# ife18_TS_BMS_Master.net
KiCad netlist of a schematic drawn in Altium Designer
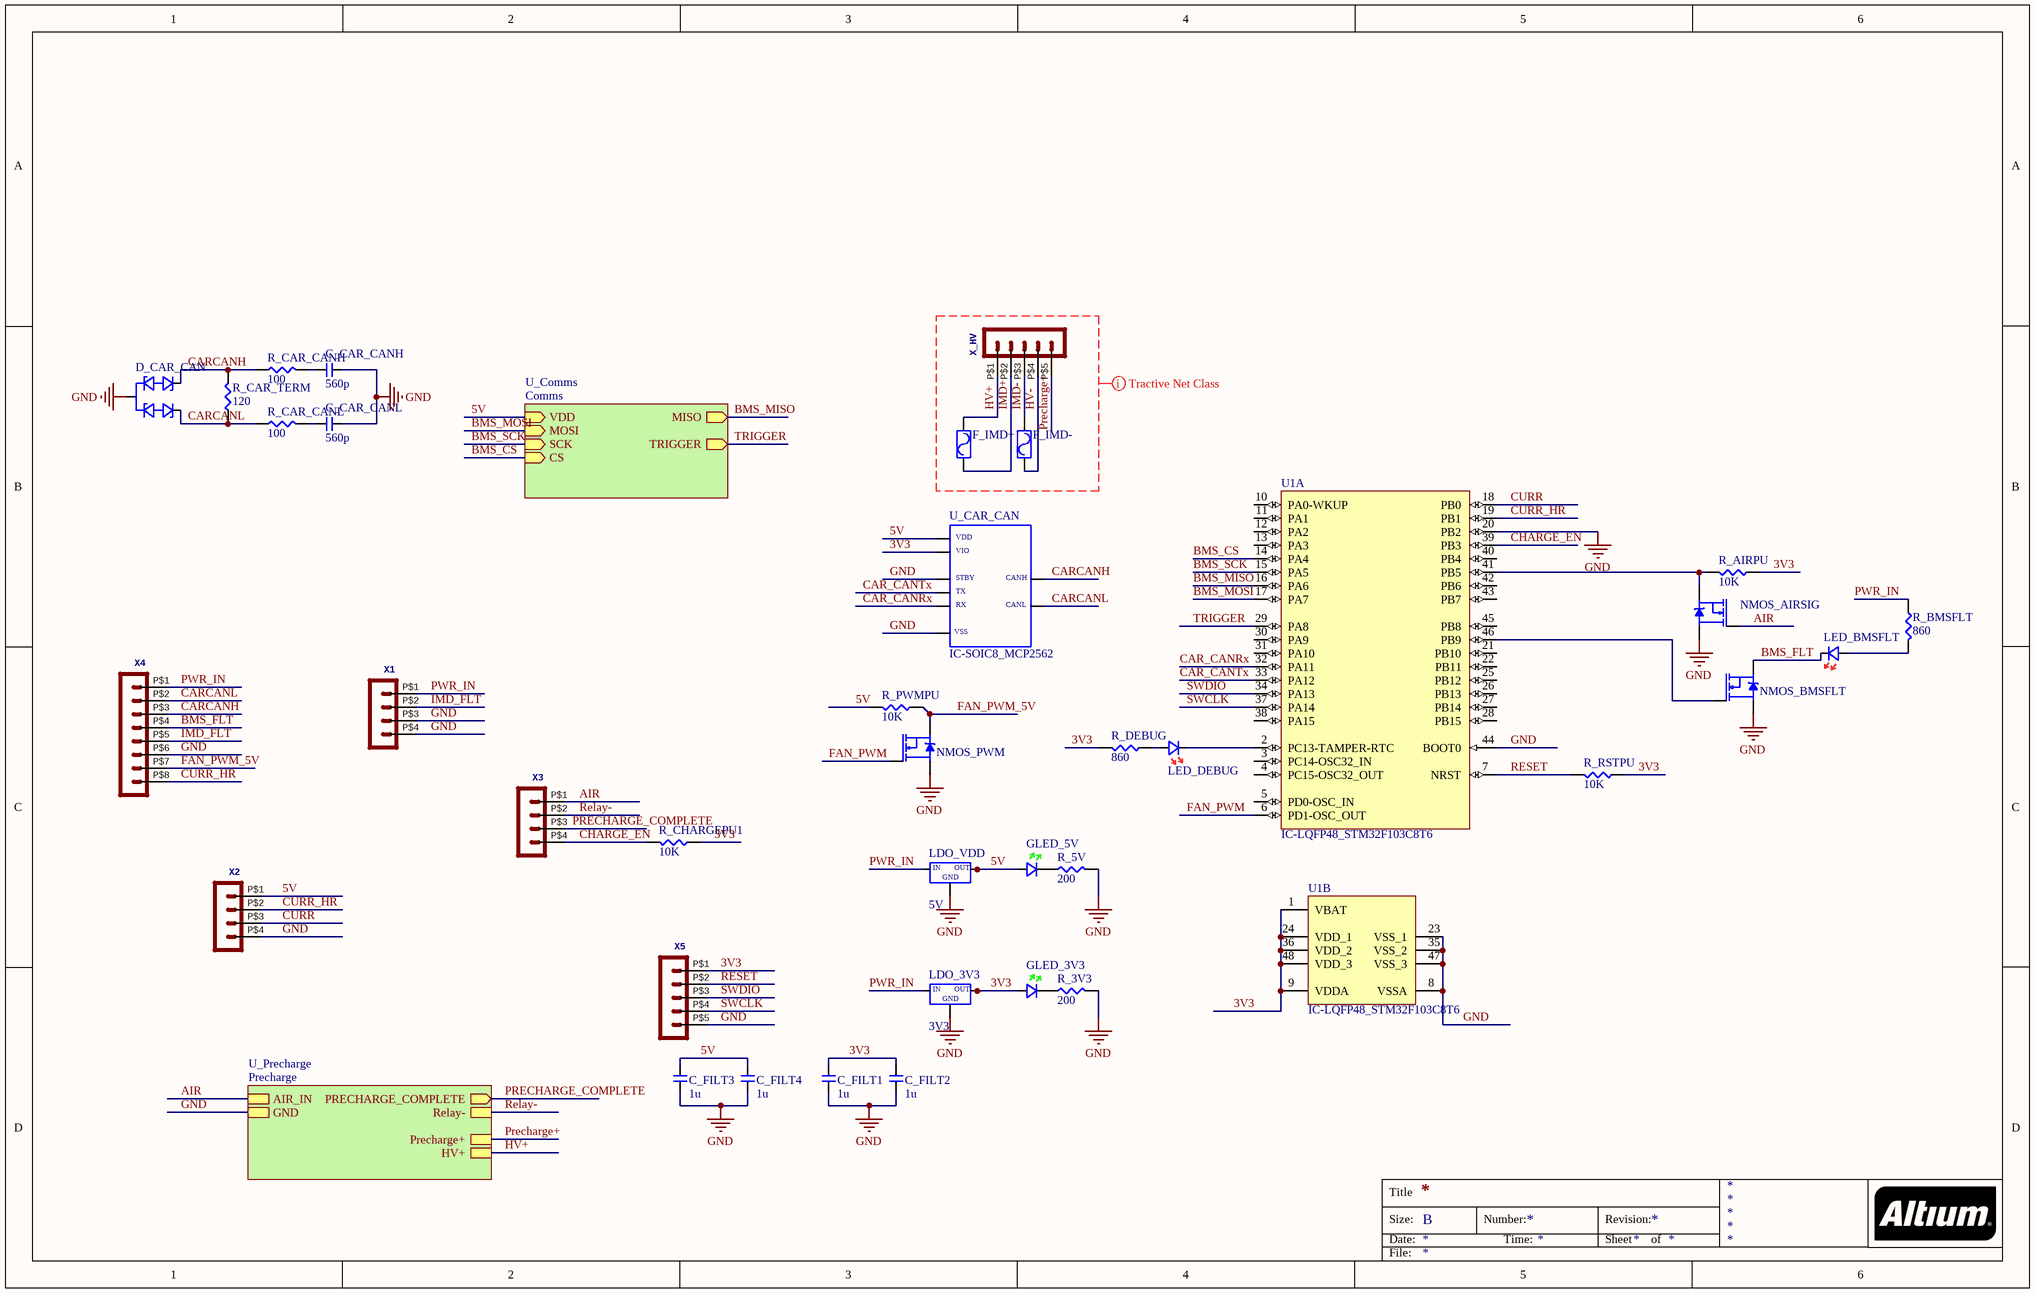
[diagram p0: ife18_TS_BMS_Master.SchDoc]

(export (version "E")
  (design (tool "Eeschema 10.0.6"))
  (components
    (comp (ref "C_CAR_CANH")
      (value "560p")
      (footprint "CAP-0603")
      (libsource (lib "altium-import") (part "root_0_CAP-0603_"))
    )
    (comp (ref "C_CAR_CANL")
      (value "560p")
      (footprint "CAP-0603")
      (libsource (lib "altium-import") (part "root_0_CAP-0603_"))
    )
    (comp (ref "C_FILT1")
      (value "1u")
      (footprint "CAP-0603")
      (libsource (lib "altium-import") (part "root_1_CAP-0603_"))
    )
    (comp (ref "C_FILT2")
      (value "1u")
      (footprint "CAP-0603")
      (libsource (lib "altium-import") (part "root_1_CAP-0603_"))
    )
    (comp (ref "C_FILT3")
      (value "1u")
      (footprint "CAP-0603")
      (libsource (lib "altium-import") (part "root_1_CAP-0603_"))
    )
    (comp (ref "C_FILT4")
      (value "1u")
      (footprint "CAP-0603")
      (libsource (lib "altium-import") (part "root_1_CAP-0603_"))
    )
    (comp (ref "D_CAR_CAN")
      (value "DIODE-SOT23_PESD1CAN")
      (footprint "SOT23")
      (libsource (lib "altium-import") (part "root_0_DIODE-SOT23_PESD1CAN_"))
    )
    (comp (ref "F_IMD+")
      (value "FUSE_885")
      (footprint "FUSE_885")
      (libsource (lib "ife19_Elec_Library") (part "FUSE_885"))
    )
    (comp (ref "F_IMD-")
      (value "FUSE_885")
      (footprint "FUSE_885")
      (libsource (lib "ife19_Elec_Library") (part "FUSE_885"))
    )
    (comp (ref "GLED_3V3")
      (value "~")
      (footprint "LEDGREEN-0603")
      (libsource (lib "altium-import") (part "root_0_LEDGREEN-0603_"))
    )
    (comp (ref "GLED_5V")
      (value "~")
      (footprint "LEDGREEN-0603")
      (libsource (lib "altium-import") (part "root_0_LEDGREEN-0603_"))
    )
    (comp (ref "LDO_3V3")
      (value "3V3")
      (footprint "SOT223")
      (libsource (lib "altium-import") (part "root_0_LDO-SOT223_SPX1117_"))
    )
    (comp (ref "LDO_VDD")
      (value "5V")
      (footprint "SOT223")
      (libsource (lib "altium-import") (part "root_0_LDO-SOT223_SPX1117_"))
    )
    (comp (ref "LED_BMSFLT")
      (value "LEDRED-0603")
      (footprint "LEDRED-0603")
      (libsource (lib "altium-import") (part "root_2_LEDRED-0603_"))
    )
    (comp (ref "LED_DEBUG")
      (value "LEDRED-0603")
      (footprint "LEDRED-0603")
      (libsource (lib "altium-import") (part "root_2_mirrored_LEDRED-0603_"))
    )
    (comp (ref "NMOS_AIRSIG")
      (value "NMOS-SOT23")
      (footprint "SOT23")
      (libsource (lib "altium-import") (part "root_0_NMOS-SOT23_"))
    )
    (comp (ref "NMOS_BMSFLT")
      (value "NMOS-SOT23")
      (footprint "SOT23")
      (libsource (lib "altium-import") (part "root_0_mirrored_NMOS-SOT23_"))
    )
    (comp (ref "NMOS_PWM")
      (value "NMOS-SOT23")
      (footprint "SOT23")
      (libsource (lib "altium-import") (part "root_0_mirrored_NMOS-SOT23_"))
    )
    (comp (ref "R_3V3")
      (value "200")
      (footprint "RES-0603")
      (libsource (lib "altium-import") (part "root_0_RES-0603_"))
    )
    (comp (ref "R_5V")
      (value "200")
      (footprint "RES-0603")
      (libsource (lib "altium-import") (part "root_0_RES-0603_"))
    )
    (comp (ref "R_AIRPU")
      (value "10K")
      (footprint "RES-0603")
      (libsource (lib "altium-import") (part "root_2_RES-0603_"))
    )
    (comp (ref "R_BMSFLT")
      (value "860")
      (footprint "RES-0603")
      (libsource (lib "altium-import") (part "root_1_mirrored_RES-0603_"))
    )
    (comp (ref "R_CAR_CANH")
      (value "100")
      (footprint "RES-0603")
      (libsource (lib "altium-import") (part "root_0_RES-0603_"))
    )
    (comp (ref "R_CAR_CANL")
      (value "100")
      (footprint "RES-0603")
      (libsource (lib "altium-import") (part "root_0_RES-0603_"))
    )
    (comp (ref "R_CAR_TERM")
      (value "120")
      (footprint "RES-0603")
      (libsource (lib "altium-import") (part "root_1_RES-0603_"))
    )
    (comp (ref "R_CHARGEPU1")
      (value "10K")
      (footprint "RES-0603")
      (libsource (lib "altium-import") (part "root_2_RES-0603_"))
    )
    (comp (ref "R_DEBUG")
      (value "860")
      (footprint "RES-0603")
      (libsource (lib "altium-import") (part "root_2_RES-0603_"))
    )
    (comp (ref "R_PWMPU")
      (value "10K")
      (footprint "RES-0603")
      (libsource (lib "altium-import") (part "root_2_mirrored_RES-0603_"))
    )
    (comp (ref "R_RSTPU")
      (value "10K")
      (footprint "RES-0603")
      (libsource (lib "altium-import") (part "root_2_RES-0603_"))
    )
    (comp (ref "U1")
      (value "IC-LQFP48_STM32F103C8T6")
      (footprint "STM-LQFP48_M")
      (fields (field (name "PARTNUMBER") "STM32F103C8T6"))
      (libsource (lib "ife19_Elec_Library") (part "IC-LQFP48_STM32F103C8T6"))
    )
    (comp (ref "U_CAR_CAN")
      (value "IC-SOIC8_MCP2562")
      (footprint "SOIC8")
      (libsource (lib "altium-import") (part "root_0_IC-SOIC8_MCP2562_"))
    )
    (comp (ref "X1")
      (value "Molex - Micro-Fit 3.0 Series connector,  3.00mm (0.118\") pitch header, 4 positions.")
      (footprint "43650-0424")
      (libsource (lib "ife19_Elec_Conn_Library") (part "POS4_MF43650-0424"))
    )
    (comp (ref "X2")
      (value "Molex - Micro-Fit 3.0 Series connector,  3.00mm (0.118\") pitch header, 4 positions.")
      (footprint "43650-0424")
      (libsource (lib "ife19_Elec_Conn_Library") (part "POS4_MF43650-0424"))
    )
    (comp (ref "X3")
      (value "Molex - Micro-Fit 3.0 Series connector,  3.00mm (0.118\") pitch header, 4 positions.")
      (footprint "43650-0424")
      (libsource (lib "ife19_Elec_Conn_Library") (part "POS4_MF43650-0424"))
    )
    (comp (ref "X4")
      (value "Molex - Micro-Fit 3.0 Series connector,  3.00mm (0.118\") pitch header, 8 positions.")
      (footprint "43650-0824")
      (libsource (lib "MOLEX Micro-Fit") (part "HEADER_POS8_?43650-0824"))
    )
    (comp (ref "X5")
      (value "~")
      (footprint "POS5_254MM_MALE")
      (libsource (lib "altium-import") (part "root_0_mirrored_POS5_254MM_MALE_"))
    )
    (comp (ref "X_HV")
      (value "Molex - Micro-Fit 3.0 Series connector,  3.00mm (0.118\") pitch header, 5 positions.")
      (footprint "43650-0524")
      (libsource (lib "ife19_Elec_Conn_Library") (part "POS5_MF43650-0524"))
    )
  )
  (nets
    (net (code "1") (name "/3V3") (class "Default")
      (node (ref "C_FILT1") (pin "2") (pinfunction "2_2") (pintype "passive"))
      (node (ref "C_FILT2") (pin "2") (pinfunction "2_2") (pintype "passive"))
      (node (ref "GLED_3V3") (pin "A") (pinfunction "A_A") (pintype "passive"))
      (node (ref "LDO_3V3") (pin "2") (pinfunction "2_2") (pintype "passive"))
      (node (ref "LDO_3V3") (pin "4") (pinfunction "4_4") (pintype "passive"))
      (node (ref "R_AIRPU") (pin "1") (pinfunction "1_1") (pintype "passive"))
      (node (ref "R_CHARGEPU1") (pin "1") (pinfunction "1_1") (pintype "passive"))
      (node (ref "R_DEBUG") (pin "2") (pinfunction "2_2") (pintype "passive"))
      (node (ref "R_RSTPU") (pin "1") (pinfunction "1_1") (pintype "passive"))
      (node (ref "U1") (pin "1") (pinfunction "VBAT_1") (pintype "power_in"))
      (node (ref "U1") (pin "24") (pinfunction "VDD_1_24") (pintype "power_in"))
      (node (ref "U1") (pin "36") (pinfunction "VDD_2_36") (pintype "power_in"))
      (node (ref "U1") (pin "48") (pinfunction "VDD_3_48") (pintype "power_in"))
      (node (ref "U1") (pin "9") (pinfunction "VDDA_9") (pintype "power_in"))
      (node (ref "U_CAR_CAN") (pin "5") (pinfunction "5_5") (pintype "passive"))
      (node (ref "X5") (pin "P$1") (pinfunction "1_P$1") (pintype "passive"))
    )
    (net (code "2") (name "/5V") (class "Default")
      (node (ref "C_FILT3") (pin "2") (pinfunction "2_2") (pintype "passive"))
      (node (ref "C_FILT4") (pin "2") (pinfunction "2_2") (pintype "passive"))
      (node (ref "GLED_5V") (pin "A") (pinfunction "A_A") (pintype "passive"))
      (node (ref "LDO_VDD") (pin "2") (pinfunction "2_2") (pintype "passive"))
      (node (ref "LDO_VDD") (pin "4") (pinfunction "4_4") (pintype "passive"))
      (node (ref "R_PWMPU") (pin "1") (pinfunction "1_1") (pintype "passive"))
      (node (ref "U_CAR_CAN") (pin "3") (pinfunction "3_3") (pintype "passive"))
      (node (ref "X2") (pin "P$1") (pinfunction "1_P$1") (pintype "passive"))
    )
    (net (code "3") (name "/AIR") (class "Default")
      (node (ref "NMOS_AIRSIG") (pin "1") (pinfunction "G_1") (pintype "passive"))
      (node (ref "X3") (pin "P$1") (pinfunction "1_P$1") (pintype "passive"))
    )
    (net (code "4") (name "/BMS_CS") (class "Default")
      (node (ref "U1") (pin "14") (pinfunction "PA4_14") (pintype "bidirectional"))
    )
    (net (code "5") (name "/BMS_FLT") (class "Default")
      (node (ref "LED_BMSFLT") (pin "K") (pinfunction "K_K") (pintype "passive"))
      (node (ref "NMOS_BMSFLT") (pin "3") (pinfunction "D_3") (pintype "passive"))
      (node (ref "X4") (pin "P$4") (pinfunction "4_P$4") (pintype "passive"))
    )
    (net (code "6") (name "/BMS_MISO") (class "Default")
      (node (ref "U1") (pin "16") (pinfunction "PA6_16") (pintype "bidirectional"))
    )
    (net (code "7") (name "/BMS_MOSI") (class "Default")
      (node (ref "U1") (pin "17") (pinfunction "PA7_17") (pintype "bidirectional"))
    )
    (net (code "8") (name "/BMS_SCK") (class "Default")
      (node (ref "U1") (pin "15") (pinfunction "PA5_15") (pintype "bidirectional"))
    )
    (net (code "9") (name "/CARCANH") (class "Default")
      (node (ref "D_CAR_CAN") (pin "2") (pinfunction "CAN2_2") (pintype "passive"))
      (node (ref "R_CAR_CANH") (pin "1") (pinfunction "1_1") (pintype "passive"))
      (node (ref "R_CAR_TERM") (pin "2") (pinfunction "2_2") (pintype "passive"))
      (node (ref "U_CAR_CAN") (pin "7") (pinfunction "7_7") (pintype "passive"))
      (node (ref "X4") (pin "P$3") (pinfunction "3_P$3") (pintype "passive"))
    )
    (net (code "10") (name "/CARCANL") (class "Default")
      (node (ref "D_CAR_CAN") (pin "1") (pinfunction "CAN1_1") (pintype "passive"))
      (node (ref "R_CAR_CANL") (pin "1") (pinfunction "1_1") (pintype "passive"))
      (node (ref "R_CAR_TERM") (pin "1") (pinfunction "1_1") (pintype "passive"))
      (node (ref "U_CAR_CAN") (pin "6") (pinfunction "6_6") (pintype "passive"))
      (node (ref "X4") (pin "P$2") (pinfunction "2_P$2") (pintype "passive"))
    )
    (net (code "11") (name "/CAR_CANRx") (class "Default")
      (node (ref "U1") (pin "32") (pinfunction "PA11_32") (pintype "bidirectional"))
      (node (ref "U_CAR_CAN") (pin "4") (pinfunction "4_4") (pintype "passive"))
    )
    (net (code "12") (name "/CAR_CANTx") (class "Default")
      (node (ref "U1") (pin "33") (pinfunction "PA12_33") (pintype "bidirectional"))
      (node (ref "U_CAR_CAN") (pin "1") (pinfunction "1_1") (pintype "passive"))
    )
    (net (code "13") (name "/CHARGE_EN") (class "Default")
      (node (ref "R_CHARGEPU1") (pin "2") (pinfunction "2_2") (pintype "passive"))
      (node (ref "U1") (pin "39") (pinfunction "PB3_39") (pintype "bidirectional"))
      (node (ref "X3") (pin "P$4") (pinfunction "4_P$4") (pintype "passive"))
    )
    (net (code "14") (name "/CURR") (class "Default")
      (node (ref "U1") (pin "18") (pinfunction "PB0_18") (pintype "bidirectional"))
      (node (ref "X2") (pin "P$3") (pinfunction "3_P$3") (pintype "passive"))
    )
    (net (code "15") (name "/CURR_HR") (class "Default")
      (node (ref "U1") (pin "19") (pinfunction "PB1_19") (pintype "bidirectional"))
      (node (ref "X2") (pin "P$2") (pinfunction "2_P$2") (pintype "passive"))
      (node (ref "X4") (pin "P$8") (pinfunction "8_P$8") (pintype "passive"))
    )
    (net (code "16") (name "/FAN_PWM") (class "Default")
      (node (ref "NMOS_PWM") (pin "1") (pinfunction "G_1") (pintype "passive"))
      (node (ref "U1") (pin "6") (pinfunction "PD1-OSC_OUT_6") (pintype "bidirectional"))
    )
    (net (code "17") (name "/FAN_PWM_5V") (class "Default")
      (node (ref "NMOS_PWM") (pin "3") (pinfunction "D_3") (pintype "passive"))
      (node (ref "R_PWMPU") (pin "2") (pinfunction "2_2") (pintype "passive"))
      (node (ref "X4") (pin "P$7") (pinfunction "7_P$7") (pintype "passive"))
    )
    (net (code "18") (name "/HV+") (class "Default")
      (node (ref "F_IMD+") (pin "1") (pinfunction "1_1") (pintype "passive"))
      (node (ref "X_HV") (pin "P$1") (pinfunction "1_P$1") (pintype "passive"))
    )
    (net (code "19") (name "/HV-") (class "Default")
      (node (ref "F_IMD-") (pin "2") (pinfunction "2_2") (pintype "passive"))
      (node (ref "X_HV") (pin "P$4") (pinfunction "4_P$4") (pintype "passive"))
    )
    (net (code "20") (name "/IMD+") (class "Default")
      (node (ref "F_IMD+") (pin "2") (pinfunction "2_2") (pintype "passive"))
      (node (ref "X_HV") (pin "P$2") (pinfunction "2_P$2") (pintype "passive"))
    )
    (net (code "21") (name "/IMD-") (class "Default")
      (node (ref "F_IMD-") (pin "1") (pinfunction "1_1") (pintype "passive"))
      (node (ref "X_HV") (pin "P$3") (pinfunction "3_P$3") (pintype "passive"))
    )
    (net (code "22") (name "/IMD_FLT") (class "Default")
      (node (ref "X1") (pin "P$2") (pinfunction "2_P$2") (pintype "passive"))
      (node (ref "X4") (pin "P$5") (pinfunction "5_P$5") (pintype "passive"))
    )
    (net (code "23") (name "/PRECHARGE_COMPLETE") (class "Default")
      (node (ref "X3") (pin "P$3") (pinfunction "3_P$3") (pintype "passive"))
    )
    (net (code "24") (name "/PWR_IN") (class "Default")
      (node (ref "LDO_3V3") (pin "3") (pinfunction "3_3") (pintype "passive"))
      (node (ref "LDO_VDD") (pin "3") (pinfunction "3_3") (pintype "passive"))
      (node (ref "R_BMSFLT") (pin "2") (pinfunction "2_2") (pintype "passive"))
      (node (ref "X1") (pin "P$1") (pinfunction "1_P$1") (pintype "passive"))
      (node (ref "X4") (pin "P$1") (pinfunction "1_P$1") (pintype "passive"))
    )
    (net (code "25") (name "/Precharge+") (class "Default")
      (node (ref "X_HV") (pin "P$5") (pinfunction "5_P$5") (pintype "passive"))
    )
    (net (code "26") (name "/RESET") (class "Default")
      (node (ref "R_RSTPU") (pin "2") (pinfunction "2_2") (pintype "passive"))
      (node (ref "U1") (pin "7") (pinfunction "NRST_7") (pintype "bidirectional"))
      (node (ref "X5") (pin "P$2") (pinfunction "2_P$2") (pintype "passive"))
    )
    (net (code "27") (name "/Relay-") (class "Default")
      (node (ref "X3") (pin "P$2") (pinfunction "2_P$2") (pintype "passive"))
    )
    (net (code "28") (name "/SWCLK") (class "Default")
      (node (ref "U1") (pin "37") (pinfunction "PA14_37") (pintype "bidirectional"))
      (node (ref "X5") (pin "P$4") (pinfunction "4_P$4") (pintype "passive"))
    )
    (net (code "29") (name "/SWDIO") (class "Default")
      (node (ref "U1") (pin "34") (pinfunction "PA13_34") (pintype "bidirectional"))
      (node (ref "X5") (pin "P$3") (pinfunction "3_P$3") (pintype "passive"))
    )
    (net (code "30") (name "/TRIGGER") (class "Default")
      (node (ref "U1") (pin "29") (pinfunction "PA8_29") (pintype "bidirectional"))
    )
    (net (code "31") (name "GND") (class "Default")
      (node (ref "C_CAR_CANH") (pin "2") (pinfunction "2_2") (pintype "passive"))
      (node (ref "C_CAR_CANL") (pin "2") (pinfunction "2_2") (pintype "passive"))
      (node (ref "C_FILT1") (pin "1") (pinfunction "1_1") (pintype "passive"))
      (node (ref "C_FILT2") (pin "1") (pinfunction "1_1") (pintype "passive"))
      (node (ref "C_FILT3") (pin "1") (pinfunction "1_1") (pintype "passive"))
      (node (ref "C_FILT4") (pin "1") (pinfunction "1_1") (pintype "passive"))
      (node (ref "D_CAR_CAN") (pin "3") (pinfunction "G_3") (pintype "passive"))
      (node (ref "LDO_3V3") (pin "1") (pinfunction "1_1") (pintype "passive"))
      (node (ref "LDO_VDD") (pin "1") (pinfunction "1_1") (pintype "passive"))
      (node (ref "NMOS_AIRSIG") (pin "2") (pinfunction "S_2") (pintype "passive"))
      (node (ref "NMOS_BMSFLT") (pin "2") (pinfunction "S_2") (pintype "passive"))
      (node (ref "NMOS_PWM") (pin "2") (pinfunction "S_2") (pintype "passive"))
      (node (ref "R_3V3") (pin "2") (pinfunction "2_2") (pintype "passive"))
      (node (ref "R_5V") (pin "2") (pinfunction "2_2") (pintype "passive"))
      (node (ref "U1") (pin "20") (pinfunction "PB2_20") (pintype "bidirectional"))
      (node (ref "U1") (pin "23") (pinfunction "VSS_1_23") (pintype "power_in"))
      (node (ref "U1") (pin "35") (pinfunction "VSS_2_35") (pintype "power_in"))
      (node (ref "U1") (pin "44") (pinfunction "BOOT0_44") (pintype "input"))
      (node (ref "U1") (pin "47") (pinfunction "VSS_3_47") (pintype "power_in"))
      (node (ref "U1") (pin "8") (pinfunction "VSSA_8") (pintype "power_in"))
      (node (ref "U_CAR_CAN") (pin "2") (pinfunction "2_2") (pintype "passive"))
      (node (ref "U_CAR_CAN") (pin "8") (pinfunction "8_8") (pintype "passive"))
      (node (ref "X1") (pin "P$3") (pinfunction "3_P$3") (pintype "passive"))
      (node (ref "X1") (pin "P$4") (pinfunction "4_P$4") (pintype "passive"))
      (node (ref "X2") (pin "P$4") (pinfunction "4_P$4") (pintype "passive"))
      (node (ref "X4") (pin "P$6") (pinfunction "6_P$6") (pintype "passive"))
      (node (ref "X5") (pin "P$5") (pinfunction "5_P$5") (pintype "passive"))
    )
    (net (code "32") (name "Net-(C_CAR_CANH-Pad1)") (class "Default")
      (node (ref "C_CAR_CANH") (pin "1") (pinfunction "1_1") (pintype "passive"))
      (node (ref "R_CAR_CANH") (pin "2") (pinfunction "2_2") (pintype "passive"))
    )
    (net (code "33") (name "Net-(C_CAR_CANL-Pad1)") (class "Default")
      (node (ref "C_CAR_CANL") (pin "1") (pinfunction "1_1") (pintype "passive"))
      (node (ref "R_CAR_CANL") (pin "2") (pinfunction "2_2") (pintype "passive"))
    )
    (net (code "34") (name "Net-(GLED_3V3-PadK)") (class "Default")
      (node (ref "GLED_3V3") (pin "K") (pinfunction "K_K") (pintype "passive"))
      (node (ref "R_3V3") (pin "1") (pinfunction "1_1") (pintype "passive"))
    )
    (net (code "35") (name "Net-(GLED_5V-PadK)") (class "Default")
      (node (ref "GLED_5V") (pin "K") (pinfunction "K_K") (pintype "passive"))
      (node (ref "R_5V") (pin "1") (pinfunction "1_1") (pintype "passive"))
    )
    (net (code "36") (name "Net-(LED_BMSFLT-PadA)") (class "Default")
      (node (ref "LED_BMSFLT") (pin "A") (pinfunction "A_A") (pintype "passive"))
      (node (ref "R_BMSFLT") (pin "1") (pinfunction "1_1") (pintype "passive"))
    )
    (net (code "37") (name "Net-(LED_DEBUG-PadA)") (class "Default")
      (node (ref "LED_DEBUG") (pin "A") (pinfunction "A_A") (pintype "passive"))
      (node (ref "R_DEBUG") (pin "1") (pinfunction "1_1") (pintype "passive"))
    )
    (net (code "38") (name "Net-(NMOS_AIRSIG-D)") (class "Default")
      (node (ref "NMOS_AIRSIG") (pin "3") (pinfunction "D_3") (pintype "passive"))
      (node (ref "R_AIRPU") (pin "2") (pinfunction "2_2") (pintype "passive"))
      (node (ref "U1") (pin "41") (pinfunction "PB5_41") (pintype "bidirectional"))
    )
    (net (code "39") (name "Net-(NMOS_BMSFLT-G)") (class "Default")
      (node (ref "NMOS_BMSFLT") (pin "1") (pinfunction "G_1") (pintype "passive"))
      (node (ref "U1") (pin "46") (pinfunction "PB9_46") (pintype "bidirectional"))
    )
    (net (code "40") (name "Net-(U1A-PC13-TAMPER-RTC)") (class "Default")
      (node (ref "LED_DEBUG") (pin "K") (pinfunction "K_K") (pintype "passive"))
      (node (ref "U1") (pin "2") (pinfunction "PC13-TAMPER-RTC_2") (pintype "bidirectional"))
    )
    (net (code "41") (name "unconnected-(U1A-PA0-WKUP-Pad10)") (class "Default")
      (node (ref "U1") (pin "10") (pinfunction "PA0-WKUP_10") (pintype "bidirectional"))
    )
    (net (code "42") (name "unconnected-(U1A-PA1-Pad11)") (class "Default")
      (node (ref "U1") (pin "11") (pinfunction "PA1_11") (pintype "bidirectional"))
    )
    (net (code "43") (name "unconnected-(U1A-PA2-Pad12)") (class "Default")
      (node (ref "U1") (pin "12") (pinfunction "PA2_12") (pintype "bidirectional"))
    )
    (net (code "44") (name "unconnected-(U1A-PA3-Pad13)") (class "Default")
      (node (ref "U1") (pin "13") (pinfunction "PA3_13") (pintype "bidirectional"))
    )
    (net (code "45") (name "unconnected-(U1A-PA9-Pad30)") (class "Default")
      (node (ref "U1") (pin "30") (pinfunction "PA9_30") (pintype "bidirectional"))
    )
    (net (code "46") (name "unconnected-(U1A-PA10-Pad31)") (class "Default")
      (node (ref "U1") (pin "31") (pinfunction "PA10_31") (pintype "bidirectional"))
    )
    (net (code "47") (name "unconnected-(U1A-PA15-Pad38)") (class "Default")
      (node (ref "U1") (pin "38") (pinfunction "PA15_38") (pintype "bidirectional"))
    )
    (net (code "48") (name "unconnected-(U1A-PB4-Pad40)") (class "Default")
      (node (ref "U1") (pin "40") (pinfunction "PB4_40") (pintype "bidirectional"))
    )
    (net (code "49") (name "unconnected-(U1A-PB6-Pad42)") (class "Default")
      (node (ref "U1") (pin "42") (pinfunction "PB6_42") (pintype "bidirectional"))
    )
    (net (code "50") (name "unconnected-(U1A-PB7-Pad43)") (class "Default")
      (node (ref "U1") (pin "43") (pinfunction "PB7_43") (pintype "bidirectional"))
    )
    (net (code "51") (name "unconnected-(U1A-PB8-Pad45)") (class "Default")
      (node (ref "U1") (pin "45") (pinfunction "PB8_45") (pintype "bidirectional"))
    )
    (net (code "52") (name "unconnected-(U1A-PB10-Pad21)") (class "Default")
      (node (ref "U1") (pin "21") (pinfunction "PB10_21") (pintype "bidirectional"))
    )
    (net (code "53") (name "unconnected-(U1A-PB11-Pad22)") (class "Default")
      (node (ref "U1") (pin "22") (pinfunction "PB11_22") (pintype "bidirectional"))
    )
    (net (code "54") (name "unconnected-(U1A-PB12-Pad25)") (class "Default")
      (node (ref "U1") (pin "25") (pinfunction "PB12_25") (pintype "bidirectional"))
    )
    (net (code "55") (name "unconnected-(U1A-PB13-Pad26)") (class "Default")
      (node (ref "U1") (pin "26") (pinfunction "PB13_26") (pintype "bidirectional"))
    )
    (net (code "56") (name "unconnected-(U1A-PB14-Pad27)") (class "Default")
      (node (ref "U1") (pin "27") (pinfunction "PB14_27") (pintype "bidirectional"))
    )
    (net (code "57") (name "unconnected-(U1A-PB15-Pad28)") (class "Default")
      (node (ref "U1") (pin "28") (pinfunction "PB15_28") (pintype "bidirectional"))
    )
    (net (code "58") (name "unconnected-(U1A-PC14-OSC32_IN-Pad3)") (class "Default")
      (node (ref "U1") (pin "3") (pinfunction "PC14-OSC32_IN_3") (pintype "bidirectional"))
    )
    (net (code "59") (name "unconnected-(U1A-PC15-OSC32_OUT-Pad4)") (class "Default")
      (node (ref "U1") (pin "4") (pinfunction "PC15-OSC32_OUT_4") (pintype "bidirectional"))
    )
    (net (code "60") (name "unconnected-(U1A-PD0-OSC_IN-Pad5)") (class "Default")
      (node (ref "U1") (pin "5") (pinfunction "PD0-OSC_IN_5") (pintype "bidirectional"))
    )
  )
)
